# PDAmpV2.net
KiCad netlist of a schematic drawn in EAGLE
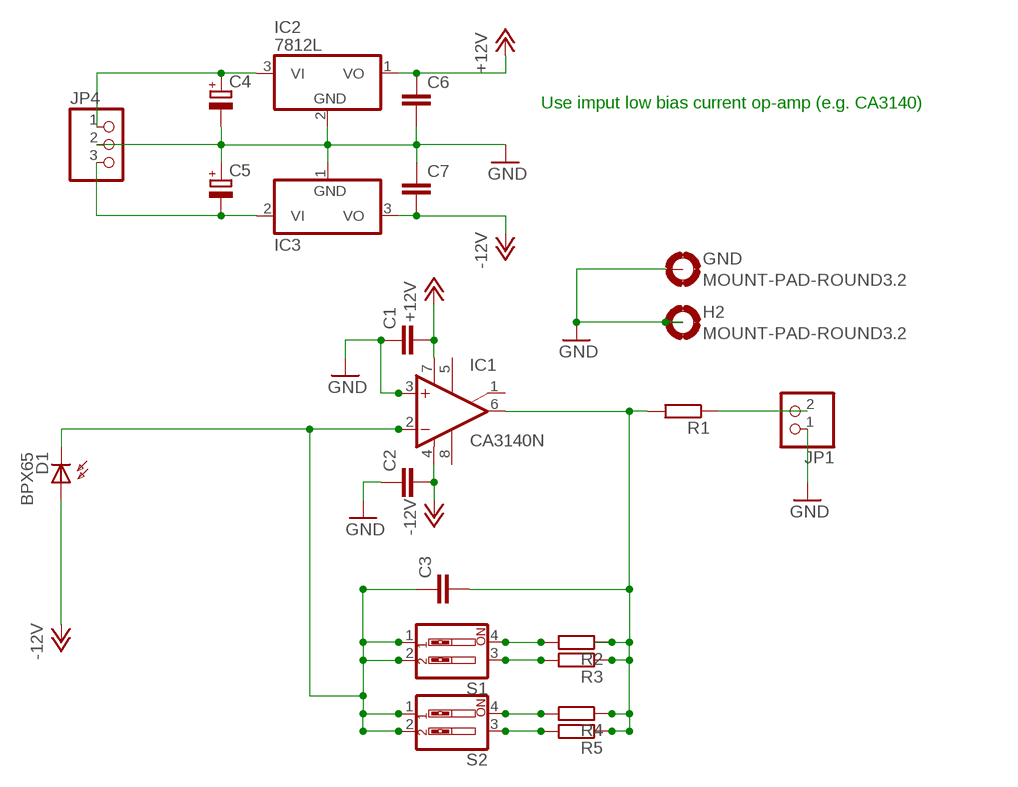
[diagram p0: schematic, sheet 1]

(export (version "E")
  (design (tool "Eeschema 10.0.6"))
  (components
    (comp (ref "C1")
      (value "C-EU025-025X050")
      (footprint "eagle-import:C025-025X050")
      (libsource (lib "eagle-import") (part "C-EU025-025X050"))
    )
    (comp (ref "C2")
      (value "C-EU025-025X050")
      (footprint "eagle-import:C025-025X050")
      (libsource (lib "eagle-import") (part "C-EU025-025X050"))
    )
    (comp (ref "C3")
      (value "C-EU050-030X075")
      (footprint "eagle-import:C050-030X075")
      (libsource (lib "eagle-import") (part "C-EU050-030X075"))
    )
    (comp (ref "C4")
      (value "CPOL-EUE5-8.5")
      (footprint "eagle-import:E5-8,5")
      (libsource (lib "eagle-import") (part "CPOL-EUE5-8.5"))
    )
    (comp (ref "C5")
      (value "CPOL-EUE5-8.5")
      (footprint "eagle-import:E5-8,5")
      (libsource (lib "eagle-import") (part "CPOL-EUE5-8.5"))
    )
    (comp (ref "C6")
      (value "C-EU050-030X075")
      (footprint "eagle-import:C050-030X075")
      (libsource (lib "eagle-import") (part "C-EU050-030X075"))
    )
    (comp (ref "C7")
      (value "C-EU050-030X075")
      (footprint "eagle-import:C050-030X075")
      (libsource (lib "eagle-import") (part "C-EU050-030X075"))
    )
    (comp (ref "D1")
      (value "BPX65")
      (footprint "eagle-import:BPX65")
      (fields (field (name "MPN") "BPX65."))
      (libsource (lib "eagle-import") (part "BPX65"))
    )
    (comp (ref "GND")
      (value "MOUNT-PAD-ROUND3.2")
      (footprint "eagle-import:3,2-PAD")
      (libsource (lib "eagle-import") (part "MOUNT-PAD-ROUND3.2"))
    )
    (comp (ref "H2")
      (value "MOUNT-PAD-ROUND3.2")
      (footprint "eagle-import:3,2-PAD")
      (libsource (lib "eagle-import") (part "MOUNT-PAD-ROUND3.2"))
    )
    (comp (ref "IC1")
      (value "CA3140N")
      (footprint "eagle-import:DIL08")
      (libsource (lib "eagle-import") (part "CA3140N"))
    )
    (comp (ref "IC2")
      (value "7812L")
      (footprint "eagle-import:TO92")
      (libsource (lib "eagle-import") (part "78L12"))
    )
    (comp (ref "IC3")
      (value "7912L")
      (footprint "eagle-import:TO92")
      (libsource (lib "eagle-import") (part "79L12"))
    )
    (comp (ref "JP1")
      (value "PINHD-1X2")
      (footprint "eagle-import:1X02")
      (libsource (lib "eagle-import") (part "PINHD-1X2"))
    )
    (comp (ref "JP4")
      (value "PINHD-1X3")
      (footprint "eagle-import:1X03")
      (libsource (lib "eagle-import") (part "PINHD-1X3"))
    )
    (comp (ref "R1")
      (value "R-EU_0207/10")
      (footprint "eagle-import:0207_10")
      (libsource (lib "eagle-import") (part "R-EU_0207/10"))
    )
    (comp (ref "R2")
      (value "R-EU_0207/10")
      (footprint "eagle-import:0207_10")
      (libsource (lib "eagle-import") (part "R-EU_0207/10"))
    )
    (comp (ref "R3")
      (value "R-EU_0207/10")
      (footprint "eagle-import:0207_10")
      (libsource (lib "eagle-import") (part "R-EU_0207/10"))
    )
    (comp (ref "R4")
      (value "R-EU_0207/10")
      (footprint "eagle-import:0207_10")
      (libsource (lib "eagle-import") (part "R-EU_0207/10"))
    )
    (comp (ref "R5")
      (value "R-EU_0207/10")
      (footprint "eagle-import:0207_10")
      (libsource (lib "eagle-import") (part "R-EU_0207/10"))
    )
    (comp (ref "S1")
      (value "SW_DIP-2")
      (footprint "eagle-import:EDG-02")
      (libsource (lib "eagle-import") (part "SW_DIP-2"))
    )
    (comp (ref "S2")
      (value "SW_DIP-2")
      (footprint "eagle-import:EDG-02")
      (libsource (lib "eagle-import") (part "SW_DIP-2"))
    )
  )
  (nets
    (net (code "1") (name "+12V") (class "Default")
      (node (ref "C1") (pin "2") (pinfunction "2_2") (pintype "passive"))
      (node (ref "C6") (pin "1") (pinfunction "1_1") (pintype "passive"))
      (node (ref "IC1") (pin "7") (pinfunction "V+_7") (pintype "power_in"))
      (node (ref "IC2") (pin "1") (pinfunction "VO_1") (pintype "passive"))
    )
    (net (code "2") (name "-12V") (class "Default")
      (node (ref "C2") (pin "2") (pinfunction "2_2") (pintype "passive"))
      (node (ref "C7") (pin "2") (pinfunction "2_2") (pintype "passive"))
      (node (ref "D1") (pin "A") (pinfunction "A_A") (pintype "passive"))
      (node (ref "IC1") (pin "4") (pinfunction "V-_4") (pintype "power_in"))
      (node (ref "IC3") (pin "3") (pinfunction "VO_3") (pintype "passive"))
    )
    (net (code "3") (name "GND") (class "Default")
      (node (ref "C1") (pin "1") (pinfunction "1_1") (pintype "passive"))
      (node (ref "C2") (pin "1") (pinfunction "1_1") (pintype "passive"))
      (node (ref "C4") (pin "-") (pinfunction "-_-") (pintype "passive"))
      (node (ref "C5") (pin "+") (pinfunction "+_+") (pintype "passive"))
      (node (ref "C6") (pin "2") (pinfunction "2_2") (pintype "passive"))
      (node (ref "C7") (pin "1") (pinfunction "1_1") (pintype "passive"))
      (node (ref "GND") (pin "B3,2") (pinfunction "MOUNT_B3,2") (pintype "passive"))
      (node (ref "H2") (pin "B3,2") (pinfunction "MOUNT_B3,2") (pintype "passive"))
      (node (ref "IC1") (pin "3") (pinfunction "+IN_3") (pintype "input"))
      (node (ref "IC2") (pin "2") (pinfunction "GND_2") (pintype "passive"))
      (node (ref "IC3") (pin "1") (pinfunction "GND_1") (pintype "passive"))
      (node (ref "JP1") (pin "1") (pinfunction "1_1") (pintype "passive"))
      (node (ref "JP4") (pin "2") (pinfunction "2_2") (pintype "passive"))
    )
    (net (code "4") (name "Net-(D1-C)") (class "Default")
      (node (ref "C3") (pin "1") (pinfunction "1_1") (pintype "passive"))
      (node (ref "D1") (pin "K") (pinfunction "C_K") (pintype "passive"))
      (node (ref "IC1") (pin "2") (pinfunction "-IN_2") (pintype "input"))
      (node (ref "S1") (pin "1") (pinfunction "1_1") (pintype "passive"))
      (node (ref "S1") (pin "2") (pinfunction "2_2") (pintype "passive"))
      (node (ref "S2") (pin "1") (pinfunction "1_1") (pintype "passive"))
      (node (ref "S2") (pin "2") (pinfunction "2_2") (pintype "passive"))
    )
    (net (code "5") (name "Net-(IC1-OUT)") (class "Default")
      (node (ref "C3") (pin "2") (pinfunction "2_2") (pintype "passive"))
      (node (ref "IC1") (pin "6") (pinfunction "OUT_6") (pintype "output"))
      (node (ref "R1") (pin "2") (pinfunction "2_2") (pintype "passive"))
      (node (ref "R2") (pin "1") (pinfunction "1_1") (pintype "passive"))
      (node (ref "R3") (pin "1") (pinfunction "1_1") (pintype "passive"))
      (node (ref "R4") (pin "1") (pinfunction "1_1") (pintype "passive"))
      (node (ref "R5") (pin "1") (pinfunction "1_1") (pintype "passive"))
    )
    (net (code "6") (name "Net-(IC2-VI)") (class "Default")
      (node (ref "C4") (pin "+") (pinfunction "+_+") (pintype "passive"))
      (node (ref "IC2") (pin "3") (pinfunction "VI_3") (pintype "input"))
      (node (ref "JP4") (pin "1") (pinfunction "1_1") (pintype "passive"))
    )
    (net (code "7") (name "Net-(IC3-VI)") (class "Default")
      (node (ref "C5") (pin "-") (pinfunction "-_-") (pintype "passive"))
      (node (ref "IC3") (pin "2") (pinfunction "VI_2") (pintype "input"))
      (node (ref "JP4") (pin "3") (pinfunction "3_3") (pintype "passive"))
    )
    (net (code "8") (name "Net-(JP1-Pad2)") (class "Default")
      (node (ref "JP1") (pin "2") (pinfunction "2_2") (pintype "passive"))
      (node (ref "R1") (pin "1") (pinfunction "1_1") (pintype "passive"))
    )
    (net (code "9") (name "Net-(R2-Pad2)") (class "Default")
      (node (ref "R2") (pin "2") (pinfunction "2_2") (pintype "passive"))
      (node (ref "S1") (pin "4") (pinfunction "4_4") (pintype "passive"))
    )
    (net (code "10") (name "Net-(R3-Pad2)") (class "Default")
      (node (ref "R3") (pin "2") (pinfunction "2_2") (pintype "passive"))
      (node (ref "S1") (pin "3") (pinfunction "3_3") (pintype "passive"))
    )
    (net (code "11") (name "Net-(R4-Pad2)") (class "Default")
      (node (ref "R4") (pin "2") (pinfunction "2_2") (pintype "passive"))
      (node (ref "S2") (pin "4") (pinfunction "4_4") (pintype "passive"))
    )
    (net (code "12") (name "Net-(R5-Pad2)") (class "Default")
      (node (ref "R5") (pin "2") (pinfunction "2_2") (pintype "passive"))
      (node (ref "S2") (pin "3") (pinfunction "3_3") (pintype "passive"))
    )
    (net (code "13") (name "unconnected-(IC1-CMP-Pad8)") (class "Default")
      (node (ref "IC1") (pin "8") (pinfunction "CMP_8") (pintype "passive"))
    )
    (net (code "14") (name "unconnected-(IC1-ON-Pad5)") (class "Default")
      (node (ref "IC1") (pin "5") (pinfunction "ON_5") (pintype "passive"))
    )
    (net (code "15") (name "unconnected-(IC1-ON{slash}CMP-Pad1)") (class "Default")
      (node (ref "IC1") (pin "1") (pinfunction "ON/CMP_1") (pintype "passive"))
    )
  )
)
